# IR_Sensor_-_6_Channels.net
KiCad netlist of a schematic drawn in EAGLE
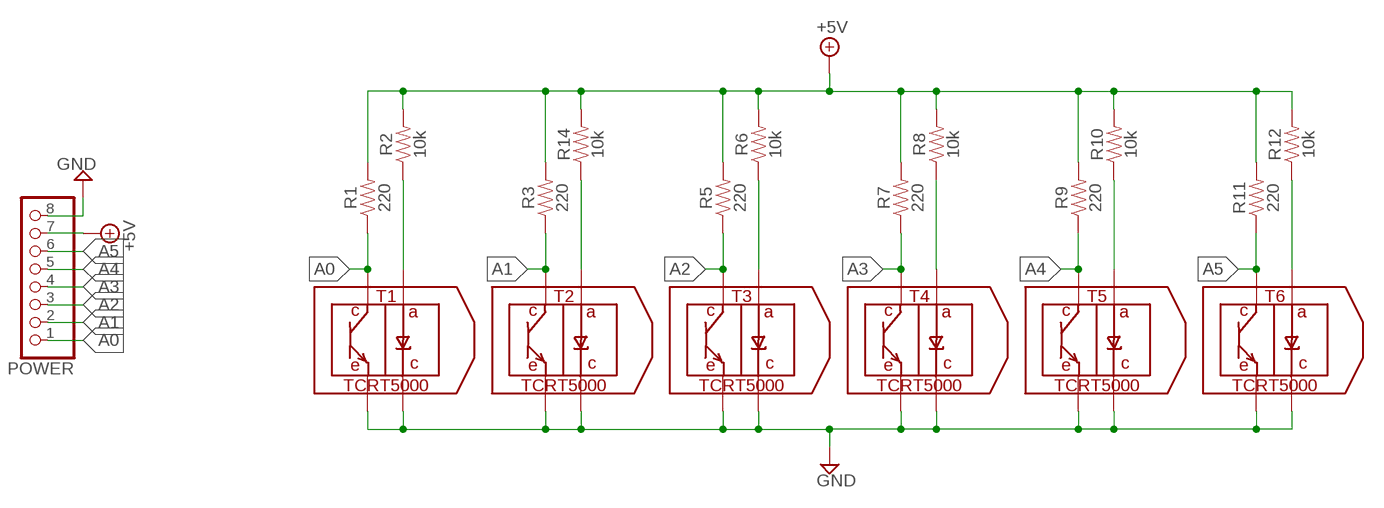
[diagram p0: schematic, sheet 1]

(export (version "E")
  (design (tool "Eeschema 10.0.6"))
  (components
    (comp (ref "POWER")
      (value "PINHD-1X8/90")
      (footprint "eagle-import:1X08_90")
      (libsource (lib "eagle-import") (part "PINHD-1X8/90"))
    )
    (comp (ref "R1")
      (value "220")
      (footprint "eagle-import:1206")
      (libsource (lib "eagle-import") (part "RESISTOR1206"))
    )
    (comp (ref "R2")
      (value "10k")
      (footprint "eagle-import:1206")
      (libsource (lib "eagle-import") (part "RESISTOR1206"))
    )
    (comp (ref "R3")
      (value "220")
      (footprint "eagle-import:1206")
      (libsource (lib "eagle-import") (part "RESISTOR1206"))
    )
    (comp (ref "R5")
      (value "220")
      (footprint "eagle-import:1206")
      (libsource (lib "eagle-import") (part "RESISTOR1206"))
    )
    (comp (ref "R6")
      (value "10k")
      (footprint "eagle-import:1206")
      (libsource (lib "eagle-import") (part "RESISTOR1206"))
    )
    (comp (ref "R7")
      (value "220")
      (footprint "eagle-import:1206")
      (libsource (lib "eagle-import") (part "RESISTOR1206"))
    )
    (comp (ref "R8")
      (value "10k")
      (footprint "eagle-import:1206")
      (libsource (lib "eagle-import") (part "RESISTOR1206"))
    )
    (comp (ref "R9")
      (value "220")
      (footprint "eagle-import:1206")
      (libsource (lib "eagle-import") (part "RESISTOR1206"))
    )
    (comp (ref "R10")
      (value "10k")
      (footprint "eagle-import:1206")
      (libsource (lib "eagle-import") (part "RESISTOR1206"))
    )
    (comp (ref "R11")
      (value "220")
      (footprint "eagle-import:1206")
      (libsource (lib "eagle-import") (part "RESISTOR1206"))
    )
    (comp (ref "R12")
      (value "10k")
      (footprint "eagle-import:1206")
      (libsource (lib "eagle-import") (part "RESISTOR1206"))
    )
    (comp (ref "R14")
      (value "10k")
      (footprint "eagle-import:1206")
      (libsource (lib "eagle-import") (part "RESISTOR1206"))
    )
    (comp (ref "T1")
      (value "TCRT5000")
      (footprint "eagle-import:5000")
      (libsource (lib "eagle-import") (part "TCRT5000"))
    )
    (comp (ref "T2")
      (value "TCRT5000")
      (footprint "eagle-import:5000")
      (libsource (lib "eagle-import") (part "TCRT5000"))
    )
    (comp (ref "T3")
      (value "TCRT5000")
      (footprint "eagle-import:5000")
      (libsource (lib "eagle-import") (part "TCRT5000"))
    )
    (comp (ref "T4")
      (value "TCRT5000")
      (footprint "eagle-import:5000")
      (libsource (lib "eagle-import") (part "TCRT5000"))
    )
    (comp (ref "T5")
      (value "TCRT5000")
      (footprint "eagle-import:5000")
      (libsource (lib "eagle-import") (part "TCRT5000"))
    )
    (comp (ref "T6")
      (value "TCRT5000")
      (footprint "eagle-import:5000")
      (libsource (lib "eagle-import") (part "TCRT5000"))
    )
  )
  (nets
    (net (code "1") (name "+5V") (class "Default")
      (node (ref "POWER") (pin "7") (pinfunction "7_7") (pintype "passive"))
      (node (ref "R1") (pin "2") (pinfunction "2_2") (pintype "passive"))
      (node (ref "R10") (pin "2") (pinfunction "2_2") (pintype "passive"))
      (node (ref "R11") (pin "2") (pinfunction "2_2") (pintype "passive"))
      (node (ref "R12") (pin "2") (pinfunction "2_2") (pintype "passive"))
      (node (ref "R14") (pin "2") (pinfunction "2_2") (pintype "passive"))
      (node (ref "R2") (pin "2") (pinfunction "2_2") (pintype "passive"))
      (node (ref "R3") (pin "2") (pinfunction "2_2") (pintype "passive"))
      (node (ref "R5") (pin "2") (pinfunction "2_2") (pintype "passive"))
      (node (ref "R6") (pin "2") (pinfunction "2_2") (pintype "passive"))
      (node (ref "R7") (pin "2") (pinfunction "2_2") (pintype "passive"))
      (node (ref "R8") (pin "2") (pinfunction "2_2") (pintype "passive"))
      (node (ref "R9") (pin "2") (pinfunction "2_2") (pintype "passive"))
    )
    (net (code "2") (name "A0") (class "Default")
      (node (ref "POWER") (pin "1") (pinfunction "1_1") (pintype "passive"))
      (node (ref "R1") (pin "1") (pinfunction "1_1") (pintype "passive"))
      (node (ref "T1") (pin "P$1") (pinfunction "P$1_P$1") (pintype "passive"))
    )
    (net (code "3") (name "A1") (class "Default")
      (node (ref "POWER") (pin "2") (pinfunction "2_2") (pintype "passive"))
      (node (ref "R3") (pin "1") (pinfunction "1_1") (pintype "passive"))
      (node (ref "T2") (pin "P$1") (pinfunction "P$1_P$1") (pintype "passive"))
    )
    (net (code "4") (name "A2") (class "Default")
      (node (ref "POWER") (pin "3") (pinfunction "3_3") (pintype "passive"))
      (node (ref "R5") (pin "1") (pinfunction "1_1") (pintype "passive"))
      (node (ref "T3") (pin "P$1") (pinfunction "P$1_P$1") (pintype "passive"))
    )
    (net (code "5") (name "A3") (class "Default")
      (node (ref "POWER") (pin "4") (pinfunction "4_4") (pintype "passive"))
      (node (ref "R7") (pin "1") (pinfunction "1_1") (pintype "passive"))
      (node (ref "T4") (pin "P$1") (pinfunction "P$1_P$1") (pintype "passive"))
    )
    (net (code "6") (name "A4") (class "Default")
      (node (ref "POWER") (pin "5") (pinfunction "5_5") (pintype "passive"))
      (node (ref "R9") (pin "1") (pinfunction "1_1") (pintype "passive"))
      (node (ref "T5") (pin "P$1") (pinfunction "P$1_P$1") (pintype "passive"))
    )
    (net (code "7") (name "A5") (class "Default")
      (node (ref "POWER") (pin "6") (pinfunction "6_6") (pintype "passive"))
      (node (ref "R11") (pin "1") (pinfunction "1_1") (pintype "passive"))
      (node (ref "T6") (pin "P$1") (pinfunction "P$1_P$1") (pintype "passive"))
    )
    (net (code "8") (name "GND") (class "Default")
      (node (ref "POWER") (pin "8") (pinfunction "8_8") (pintype "passive"))
      (node (ref "T1") (pin "P$2") (pinfunction "P$2_P$2") (pintype "passive"))
      (node (ref "T1") (pin "P$4") (pinfunction "P$4_P$4") (pintype "passive"))
      (node (ref "T2") (pin "P$2") (pinfunction "P$2_P$2") (pintype "passive"))
      (node (ref "T2") (pin "P$4") (pinfunction "P$4_P$4") (pintype "passive"))
      (node (ref "T3") (pin "P$2") (pinfunction "P$2_P$2") (pintype "passive"))
      (node (ref "T3") (pin "P$4") (pinfunction "P$4_P$4") (pintype "passive"))
      (node (ref "T4") (pin "P$2") (pinfunction "P$2_P$2") (pintype "passive"))
      (node (ref "T4") (pin "P$4") (pinfunction "P$4_P$4") (pintype "passive"))
      (node (ref "T5") (pin "P$2") (pinfunction "P$2_P$2") (pintype "passive"))
      (node (ref "T5") (pin "P$4") (pinfunction "P$4_P$4") (pintype "passive"))
      (node (ref "T6") (pin "P$2") (pinfunction "P$2_P$2") (pintype "passive"))
      (node (ref "T6") (pin "P$4") (pinfunction "P$4_P$4") (pintype "passive"))
    )
    (net (code "9") (name "Net-(R2-Pad1)") (class "Default")
      (node (ref "R2") (pin "1") (pinfunction "1_1") (pintype "passive"))
      (node (ref "T1") (pin "P$3") (pinfunction "P$3_P$3") (pintype "passive"))
    )
    (net (code "10") (name "Net-(R6-Pad1)") (class "Default")
      (node (ref "R6") (pin "1") (pinfunction "1_1") (pintype "passive"))
      (node (ref "T3") (pin "P$3") (pinfunction "P$3_P$3") (pintype "passive"))
    )
    (net (code "11") (name "Net-(R8-Pad1)") (class "Default")
      (node (ref "R8") (pin "1") (pinfunction "1_1") (pintype "passive"))
      (node (ref "T4") (pin "P$3") (pinfunction "P$3_P$3") (pintype "passive"))
    )
    (net (code "12") (name "Net-(R10-Pad1)") (class "Default")
      (node (ref "R10") (pin "1") (pinfunction "1_1") (pintype "passive"))
      (node (ref "T5") (pin "P$3") (pinfunction "P$3_P$3") (pintype "passive"))
    )
    (net (code "13") (name "Net-(R12-Pad1)") (class "Default")
      (node (ref "R12") (pin "1") (pinfunction "1_1") (pintype "passive"))
      (node (ref "T6") (pin "P$3") (pinfunction "P$3_P$3") (pintype "passive"))
    )
    (net (code "14") (name "Net-(R14-Pad1)") (class "Default")
      (node (ref "R14") (pin "1") (pinfunction "1_1") (pintype "passive"))
      (node (ref "T2") (pin "P$3") (pinfunction "P$3_P$3") (pintype "passive"))
    )
  )
)
